# wifi_thermo_v1_0.net
KiCad netlist of a schematic drawn in EAGLE
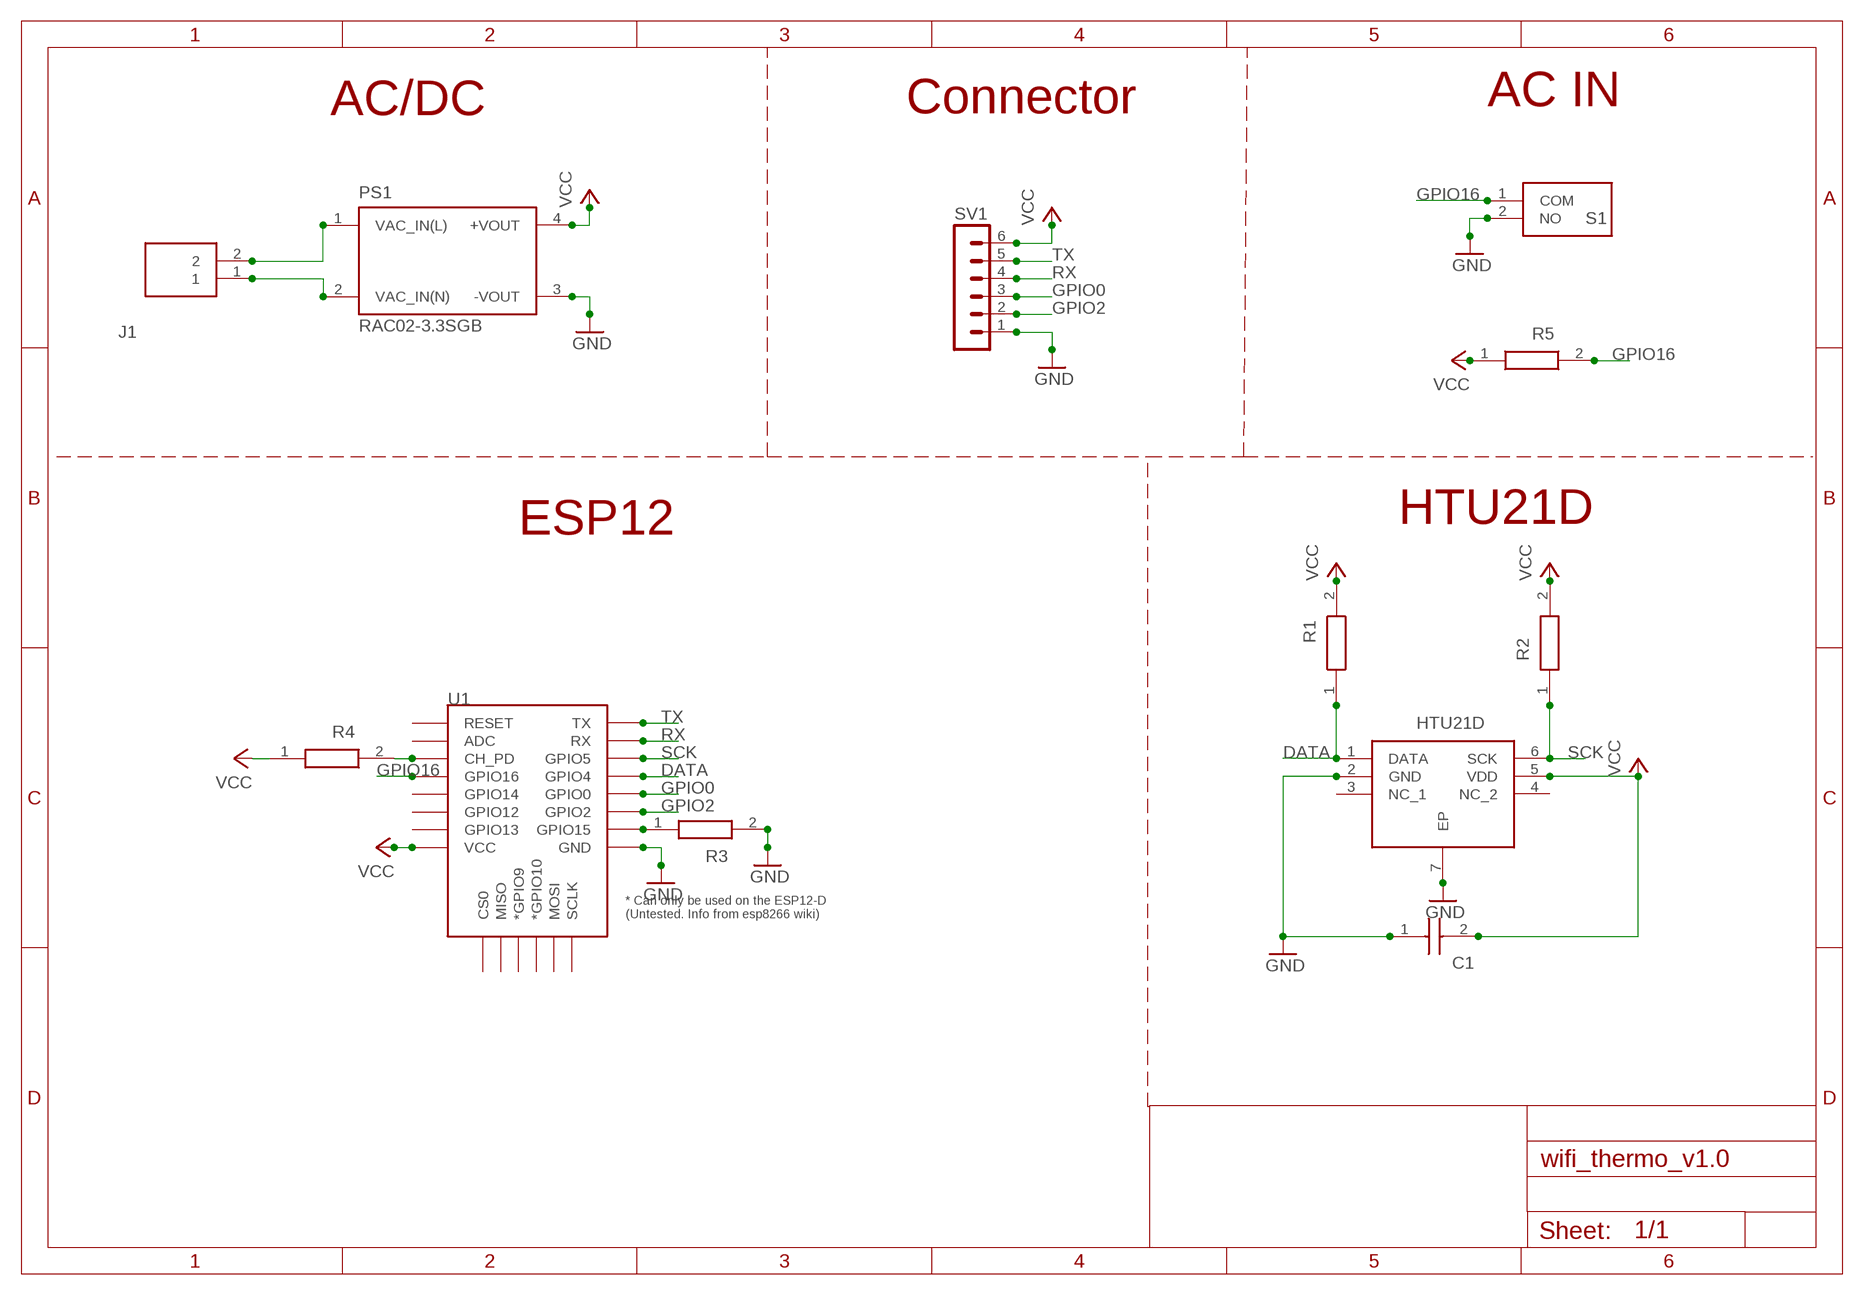
[diagram p0: schematic, sheet 1]

(export (version "E")
  (design (tool "Eeschema 10.0.6"))
  (components
    (comp (ref "C1")
      (value "C1206C104J3GEC7210")
      (footprint "eagle-import:CAPC3216X110N")
      (fields (field (name "MOUSER_PART_NUMBER") "80-C1206C104J3GECLR"))
      (libsource (lib "eagle-import") (part "C1206C104J3GEC7210"))
    )
    (comp (ref "HM1")
      (value "HTU21D")
      (footprint "eagle-import:SON100P300X300X100-7N")
      (fields (field (name "MOUSER_PART_NUMBER") "824-HTU21D"))
      (libsource (lib "eagle-import") (part "HTU21D"))
    )
    (comp (ref "J1")
      (value "TB006-508-02BE")
      (footprint "eagle-import:TB00650802BE")
      (fields (field (name "MOUSER_PART_NUMBER") "490-TB006-508-02BE"))
      (libsource (lib "eagle-import") (part "TB006-508-02BE"))
    )
    (comp (ref "PS1")
      (value "RAC02-3.3SGB")
      (footprint "eagle-import:CONV_RAC02-3.3SGB")
      (fields (field (name "MF") "Recom Power"))
      (libsource (lib "eagle-import") (part "RAC02-3.3SGB"))
    )
    (comp (ref "R1")
      (value "RT1206FRD0710KL")
      (footprint "eagle-import:RESC3116X65N")
      (fields (field (name "MOUSER_PART_NUMBER") "603-RT1206FRD0710KL"))
      (libsource (lib "eagle-import") (part "RT1206FRD0710KL"))
    )
    (comp (ref "R2")
      (value "RT1206FRD0710KL")
      (footprint "eagle-import:RESC3116X65N")
      (fields (field (name "MOUSER_PART_NUMBER") "603-RT1206FRD0710KL"))
      (libsource (lib "eagle-import") (part "RT1206FRD0710KL"))
    )
    (comp (ref "R3")
      (value "RT1206FRD0710KL")
      (footprint "eagle-import:RESC3116X65N")
      (fields (field (name "MOUSER_PART_NUMBER") "603-RT1206FRD0710KL"))
      (libsource (lib "eagle-import") (part "RT1206FRD0710KL"))
    )
    (comp (ref "R4")
      (value "RT1206FRD0710KL")
      (footprint "eagle-import:RESC3116X65N")
      (fields (field (name "MOUSER_PART_NUMBER") "603-RT1206FRD0710KL"))
      (libsource (lib "eagle-import") (part "RT1206FRD0710KL"))
    )
    (comp (ref "R5")
      (value "RT1206FRD0710KL")
      (footprint "eagle-import:RESC3116X65N")
      (fields (field (name "MOUSER_PART_NUMBER") "603-RT1206FRD0710KL"))
      (libsource (lib "eagle-import") (part "RT1206FRD0710KL"))
    )
    (comp (ref "S1")
      (value "PTS636_SP50_SMTR_LFS")
      (footprint "eagle-import:PTS636SP50SMTRLFS")
      (fields
        (field (name "MANUFACTURER_PART_NUMBER") "PTS636 SP50 SMTR LFS")
        (field (name "MOUSER_PART_NUMBER") "611-PTS636SP50SMTRLF")
      )
      (libsource (lib "eagle-import") (part "PTS636_SP50_SMTR_LFS"))
    )
    (comp (ref "SV1")
      (value "MA06-1")
      (footprint "eagle-import:MA06-1")
      (libsource (lib "eagle-import") (part "MA06-1"))
    )
    (comp (ref "U1")
      (value "ESP12ESMD")
      (footprint "eagle-import:ESP12E-SMD")
      (libsource (lib "eagle-import") (part "ESP12ESMD"))
    )
  )
  (nets
    (net (code "1") (name "/DATA") (class "Default")
      (node (ref "HM1") (pin "1") (pinfunction "DATA_1") (pintype "bidirectional"))
      (node (ref "R1") (pin "1") (pinfunction "1_1") (pintype "bidirectional"))
      (node (ref "U1") (pin "GPIO4") (pinfunction "GPIO4_GPIO4") (pintype "bidirectional"))
    )
    (net (code "2") (name "/GPIO0") (class "Default")
      (node (ref "SV1") (pin "3") (pinfunction "3_3") (pintype "passive"))
      (node (ref "U1") (pin "GPIO0") (pinfunction "GPIO0_GPIO0") (pintype "bidirectional"))
    )
    (net (code "3") (name "/GPIO2") (class "Default")
      (node (ref "SV1") (pin "2") (pinfunction "2_2") (pintype "passive"))
      (node (ref "U1") (pin "GPIO2") (pinfunction "GPIO2_GPIO2") (pintype "bidirectional"))
    )
    (net (code "4") (name "/GPIO16") (class "Default")
      (node (ref "R5") (pin "2") (pinfunction "2_2") (pintype "bidirectional"))
      (node (ref "S1") (pin "1") (pinfunction "COM_1") (pintype "bidirectional"))
      (node (ref "U1") (pin "GPIO16") (pinfunction "GPIO16_GPIO16") (pintype "bidirectional"))
    )
    (net (code "5") (name "/RX") (class "Default")
      (node (ref "SV1") (pin "4") (pinfunction "4_4") (pintype "passive"))
      (node (ref "U1") (pin "RXD0") (pinfunction "RX_RXD0") (pintype "bidirectional"))
    )
    (net (code "6") (name "/SCK") (class "Default")
      (node (ref "HM1") (pin "6") (pinfunction "SCK_6") (pintype "bidirectional"))
      (node (ref "R2") (pin "1") (pinfunction "1_1") (pintype "bidirectional"))
      (node (ref "U1") (pin "GPIO5") (pinfunction "GPIO5_GPIO5") (pintype "bidirectional"))
    )
    (net (code "7") (name "/TX") (class "Default")
      (node (ref "SV1") (pin "5") (pinfunction "5_5") (pintype "passive"))
      (node (ref "U1") (pin "TXD0") (pinfunction "TX_TXD0") (pintype "bidirectional"))
    )
    (net (code "8") (name "GND") (class "Default")
      (node (ref "C1") (pin "1") (pinfunction "1_1") (pintype "bidirectional"))
      (node (ref "HM1") (pin "2") (pinfunction "GND_2") (pintype "bidirectional"))
      (node (ref "HM1") (pin "7") (pinfunction "EP_7") (pintype "bidirectional"))
      (node (ref "PS1") (pin "3") (pinfunction "-VOUT_3") (pintype "output"))
      (node (ref "R3") (pin "2") (pinfunction "2_2") (pintype "bidirectional"))
      (node (ref "S1") (pin "2") (pinfunction "NO_2") (pintype "bidirectional"))
      (node (ref "SV1") (pin "1") (pinfunction "1_1") (pintype "passive"))
      (node (ref "U1") (pin "GND") (pinfunction "GND_GND") (pintype "bidirectional"))
    )
    (net (code "9") (name "Net-(PS1-VAC_IN(L))") (class "Default")
      (node (ref "J1") (pin "2") (pinfunction "2_2") (pintype "bidirectional"))
      (node (ref "PS1") (pin "1") (pinfunction "VAC_IN(L)_1") (pintype "input"))
    )
    (net (code "10") (name "Net-(PS1-VAC_IN(N))") (class "Default")
      (node (ref "J1") (pin "1") (pinfunction "1_1") (pintype "bidirectional"))
      (node (ref "PS1") (pin "2") (pinfunction "VAC_IN(N)_2") (pintype "input"))
    )
    (net (code "11") (name "Net-(R3-Pad1)") (class "Default")
      (node (ref "R3") (pin "1") (pinfunction "1_1") (pintype "bidirectional"))
      (node (ref "U1") (pin "GPIO15") (pinfunction "GPIO15_GPIO15") (pintype "bidirectional"))
    )
    (net (code "12") (name "Net-(R4-Pad2)") (class "Default")
      (node (ref "R4") (pin "2") (pinfunction "2_2") (pintype "bidirectional"))
      (node (ref "U1") (pin "CH_PD") (pinfunction "CH_PD_CH_PD") (pintype "bidirectional"))
    )
    (net (code "13") (name "VCC") (class "Default")
      (node (ref "C1") (pin "2") (pinfunction "2_2") (pintype "bidirectional"))
      (node (ref "HM1") (pin "5") (pinfunction "VDD_5") (pintype "bidirectional"))
      (node (ref "PS1") (pin "4") (pinfunction "+VOUT_4") (pintype "output"))
      (node (ref "R1") (pin "2") (pinfunction "2_2") (pintype "bidirectional"))
      (node (ref "R2") (pin "2") (pinfunction "2_2") (pintype "bidirectional"))
      (node (ref "R4") (pin "1") (pinfunction "1_1") (pintype "bidirectional"))
      (node (ref "R5") (pin "1") (pinfunction "1_1") (pintype "bidirectional"))
      (node (ref "SV1") (pin "6") (pinfunction "6_6") (pintype "passive"))
      (node (ref "U1") (pin "VCC") (pinfunction "VCC_VCC") (pintype "bidirectional"))
    )
    (net (code "14") (name "unconnected-(HM1-NC_1-Pad3)") (class "Default")
      (node (ref "HM1") (pin "3") (pinfunction "NC_1_3") (pintype "bidirectional"))
    )
    (net (code "15") (name "unconnected-(HM1-NC_2-Pad4)") (class "Default")
      (node (ref "HM1") (pin "4") (pinfunction "NC_2_4") (pintype "bidirectional"))
    )
    (net (code "16") (name "unconnected-(U1-*GPIO9-PadGPIO9)") (class "Default")
      (node (ref "U1") (pin "GPIO9") (pinfunction "*GPIO9_GPIO9") (pintype "bidirectional"))
    )
    (net (code "17") (name "unconnected-(U1-*GPIO10-PadGPIO10)") (class "Default")
      (node (ref "U1") (pin "GPIO10") (pinfunction "*GPIO10_GPIO10") (pintype "bidirectional"))
    )
    (net (code "18") (name "unconnected-(U1-PadADC)") (class "Default")
      (node (ref "U1") (pin "ADC") (pinfunction "ADC_ADC") (pintype "bidirectional"))
    )
    (net (code "19") (name "unconnected-(U1-PadCS0)") (class "Default")
      (node (ref "U1") (pin "CS0") (pinfunction "CS0_CS0") (pintype "bidirectional"))
    )
    (net (code "20") (name "unconnected-(U1-PadGPIO12)") (class "Default")
      (node (ref "U1") (pin "GPIO12") (pinfunction "GPIO12_GPIO12") (pintype "bidirectional"))
    )
    (net (code "21") (name "unconnected-(U1-PadGPIO13)") (class "Default")
      (node (ref "U1") (pin "GPIO13") (pinfunction "GPIO13_GPIO13") (pintype "bidirectional"))
    )
    (net (code "22") (name "unconnected-(U1-PadGPIO14)") (class "Default")
      (node (ref "U1") (pin "GPIO14") (pinfunction "GPIO14_GPIO14") (pintype "bidirectional"))
    )
    (net (code "23") (name "unconnected-(U1-PadMISO)") (class "Default")
      (node (ref "U1") (pin "MISO") (pinfunction "MISO_MISO") (pintype "bidirectional"))
    )
    (net (code "24") (name "unconnected-(U1-PadMOSI)") (class "Default")
      (node (ref "U1") (pin "MOSI") (pinfunction "MOSI_MOSI") (pintype "bidirectional"))
    )
    (net (code "25") (name "unconnected-(U1-PadRESET)") (class "Default")
      (node (ref "U1") (pin "RESET") (pinfunction "RESET_RESET") (pintype "bidirectional"))
    )
    (net (code "26") (name "unconnected-(U1-PadSCLK)") (class "Default")
      (node (ref "U1") (pin "SCLK") (pinfunction "SCLK_SCLK") (pintype "bidirectional"))
    )
  )
)
